# Snippet_ISO7221_ULN2003.net
KiCad netlist of a schematic drawn in Altium Designer
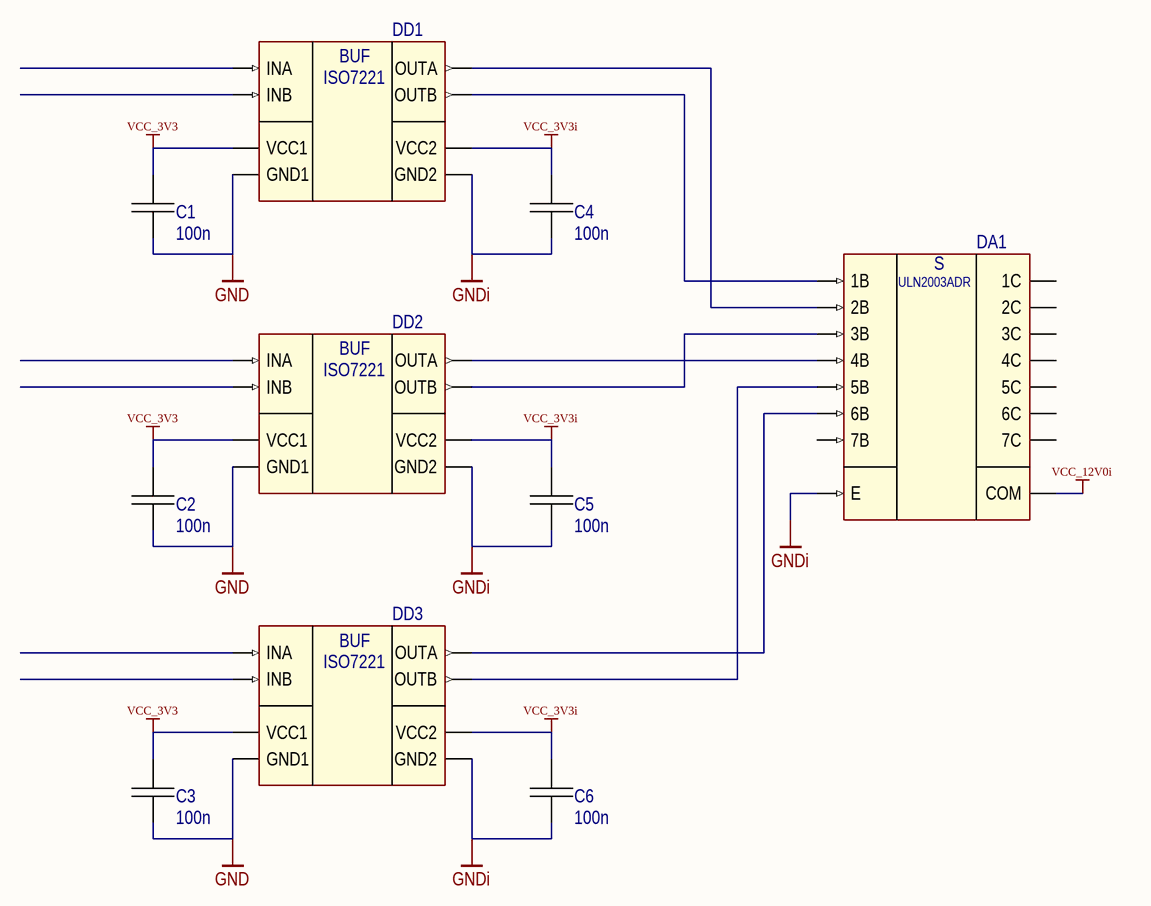
[diagram p0: Snippet_ISO7221+ULN2003.SchDoc]

(export (version "E")
  (design (tool "Eeschema 10.0.6"))
  (components
    (comp (ref "C1")
      (value "100n")
      (footprint "Capacitor_0805")
      (libsource (lib "Библиотека элементов") (part "Capacitor_0805"))
    )
    (comp (ref "C2")
      (value "100n")
      (footprint "Capacitor_0805")
      (libsource (lib "Библиотека элементов") (part "Capacitor_0805"))
    )
    (comp (ref "C3")
      (value "100n")
      (footprint "Capacitor_0805")
      (libsource (lib "Библиотека элементов") (part "Capacitor_0805"))
    )
    (comp (ref "C4")
      (value "100n")
      (footprint "Capacitor_0805")
      (libsource (lib "Библиотека элементов") (part "Capacitor_0805"))
    )
    (comp (ref "C5")
      (value "100n")
      (footprint "Capacitor_0805")
      (libsource (lib "Библиотека элементов") (part "Capacitor_0805"))
    )
    (comp (ref "C6")
      (value "100n")
      (footprint "Capacitor_0805")
      (libsource (lib "Библиотека элементов") (part "Capacitor_0805"))
    )
    (comp (ref "DA1")
      (value "ULN2003")
      (footprint "MCP3208_SOIC16")
      (libsource (lib "Библиотека элементов") (part "ULN2003"))
    )
    (comp (ref "DD1")
      (value "ISO7221")
      (footprint "ISO7221")
      (libsource (lib "Библиотека элементов") (part "ISO7221"))
    )
    (comp (ref "DD2")
      (value "ISO7221")
      (footprint "ISO7221")
      (libsource (lib "Библиотека элементов") (part "ISO7221"))
    )
    (comp (ref "DD3")
      (value "ISO7221")
      (footprint "ISO7221")
      (libsource (lib "Библиотека элементов") (part "ISO7221"))
    )
  )
  (nets
    (net (code "1") (name "GND") (class "Default")
      (node (ref "C1") (pin "2") (pinfunction "2_2") (pintype "passive"))
      (node (ref "C2") (pin "2") (pinfunction "2_2") (pintype "passive"))
      (node (ref "C3") (pin "2") (pinfunction "2_2") (pintype "passive"))
      (node (ref "DD1") (pin "4") (pinfunction "GND1_4") (pintype "power_in"))
      (node (ref "DD2") (pin "4") (pinfunction "GND1_4") (pintype "power_in"))
      (node (ref "DD3") (pin "4") (pinfunction "GND1_4") (pintype "power_in"))
    )
    (net (code "2") (name "GNDi") (class "Default")
      (node (ref "C4") (pin "2") (pinfunction "2_2") (pintype "passive"))
      (node (ref "C5") (pin "2") (pinfunction "2_2") (pintype "passive"))
      (node (ref "C6") (pin "2") (pinfunction "2_2") (pintype "passive"))
      (node (ref "DA1") (pin "8") (pinfunction "E_8") (pintype "input"))
      (node (ref "DD1") (pin "5") (pinfunction "GND2_5") (pintype "power_in"))
      (node (ref "DD2") (pin "5") (pinfunction "GND2_5") (pintype "power_in"))
      (node (ref "DD3") (pin "5") (pinfunction "GND2_5") (pintype "power_in"))
    )
    (net (code "3") (name "Net-(DA1-1B)") (class "Default")
      (node (ref "DA1") (pin "1") (pinfunction "1B_1") (pintype "input"))
      (node (ref "DD1") (pin "6") (pinfunction "OUTB_6") (pintype "output"))
    )
    (net (code "4") (name "Net-(DA1-2B)") (class "Default")
      (node (ref "DA1") (pin "2") (pinfunction "2B_2") (pintype "input"))
      (node (ref "DD1") (pin "2") (pinfunction "OUTA_2") (pintype "output"))
    )
    (net (code "5") (name "Net-(DA1-3B)") (class "Default")
      (node (ref "DA1") (pin "3") (pinfunction "3B_3") (pintype "input"))
      (node (ref "DD2") (pin "6") (pinfunction "OUTB_6") (pintype "output"))
    )
    (net (code "6") (name "Net-(DA1-4B)") (class "Default")
      (node (ref "DA1") (pin "4") (pinfunction "4B_4") (pintype "input"))
      (node (ref "DD2") (pin "2") (pinfunction "OUTA_2") (pintype "output"))
    )
    (net (code "7") (name "Net-(DA1-5B)") (class "Default")
      (node (ref "DA1") (pin "5") (pinfunction "5B_5") (pintype "input"))
      (node (ref "DD3") (pin "6") (pinfunction "OUTB_6") (pintype "output"))
    )
    (net (code "8") (name "Net-(DA1-6B)") (class "Default")
      (node (ref "DA1") (pin "6") (pinfunction "6B_6") (pintype "input"))
      (node (ref "DD3") (pin "2") (pinfunction "OUTA_2") (pintype "output"))
    )
    (net (code "9") (name "VCC_3V3") (class "Default")
      (node (ref "C1") (pin "1") (pinfunction "1_1") (pintype "passive"))
      (node (ref "C2") (pin "1") (pinfunction "1_1") (pintype "passive"))
      (node (ref "C3") (pin "1") (pinfunction "1_1") (pintype "passive"))
      (node (ref "DD1") (pin "1") (pinfunction "VCC1_1") (pintype "power_in"))
      (node (ref "DD2") (pin "1") (pinfunction "VCC1_1") (pintype "power_in"))
      (node (ref "DD3") (pin "1") (pinfunction "VCC1_1") (pintype "power_in"))
    )
    (net (code "10") (name "VCC_3V3i") (class "Default")
      (node (ref "C4") (pin "1") (pinfunction "1_1") (pintype "passive"))
      (node (ref "C5") (pin "1") (pinfunction "1_1") (pintype "passive"))
      (node (ref "C6") (pin "1") (pinfunction "1_1") (pintype "passive"))
      (node (ref "DD1") (pin "8") (pinfunction "VCC2_8") (pintype "power_in"))
      (node (ref "DD2") (pin "8") (pinfunction "VCC2_8") (pintype "power_in"))
      (node (ref "DD3") (pin "8") (pinfunction "VCC2_8") (pintype "power_in"))
    )
    (net (code "11") (name "VCC_12V0i") (class "Default")
      (node (ref "DA1") (pin "9") (pinfunction "COM_9") (pintype "power_in"))
    )
    (net (code "12") (name "unconnected-(DA1-1C-Pad16)") (class "Default")
      (node (ref "DA1") (pin "16") (pinfunction "1C_16") (pintype "open_collector"))
    )
    (net (code "13") (name "unconnected-(DA1-2C-Pad15)") (class "Default")
      (node (ref "DA1") (pin "15") (pinfunction "2C_15") (pintype "open_collector"))
    )
    (net (code "14") (name "unconnected-(DA1-3C-Pad14)") (class "Default")
      (node (ref "DA1") (pin "14") (pinfunction "3C_14") (pintype "open_collector"))
    )
    (net (code "15") (name "unconnected-(DA1-4C-Pad13)") (class "Default")
      (node (ref "DA1") (pin "13") (pinfunction "4C_13") (pintype "open_collector"))
    )
    (net (code "16") (name "unconnected-(DA1-5C-Pad12)") (class "Default")
      (node (ref "DA1") (pin "12") (pinfunction "5C_12") (pintype "open_collector"))
    )
    (net (code "17") (name "unconnected-(DA1-6C-Pad11)") (class "Default")
      (node (ref "DA1") (pin "11") (pinfunction "6C_11") (pintype "open_collector"))
    )
    (net (code "18") (name "unconnected-(DA1-7B-Pad7)") (class "Default")
      (node (ref "DA1") (pin "7") (pinfunction "7B_7") (pintype "input"))
    )
    (net (code "19") (name "unconnected-(DA1-7C-Pad10)") (class "Default")
      (node (ref "DA1") (pin "10") (pinfunction "7C_10") (pintype "open_collector"))
    )
    (net (code "20") (name "unconnected-(DD1-INA-Pad7)") (class "Default")
      (node (ref "DD1") (pin "7") (pinfunction "INA_7") (pintype "input"))
    )
    (net (code "21") (name "unconnected-(DD1-INB-Pad3)") (class "Default")
      (node (ref "DD1") (pin "3") (pinfunction "INB_3") (pintype "input"))
    )
    (net (code "22") (name "unconnected-(DD2-INA-Pad7)") (class "Default")
      (node (ref "DD2") (pin "7") (pinfunction "INA_7") (pintype "input"))
    )
    (net (code "23") (name "unconnected-(DD2-INB-Pad3)") (class "Default")
      (node (ref "DD2") (pin "3") (pinfunction "INB_3") (pintype "input"))
    )
    (net (code "24") (name "unconnected-(DD3-INA-Pad7)") (class "Default")
      (node (ref "DD3") (pin "7") (pinfunction "INA_7") (pintype "input"))
    )
    (net (code "25") (name "unconnected-(DD3-INB-Pad3)") (class "Default")
      (node (ref "DD3") (pin "3") (pinfunction "INB_3") (pintype "input"))
    )
  )
)
